# Universal_Receiver.net
KiCad netlist of a schematic drawn in EasyEDA Pro
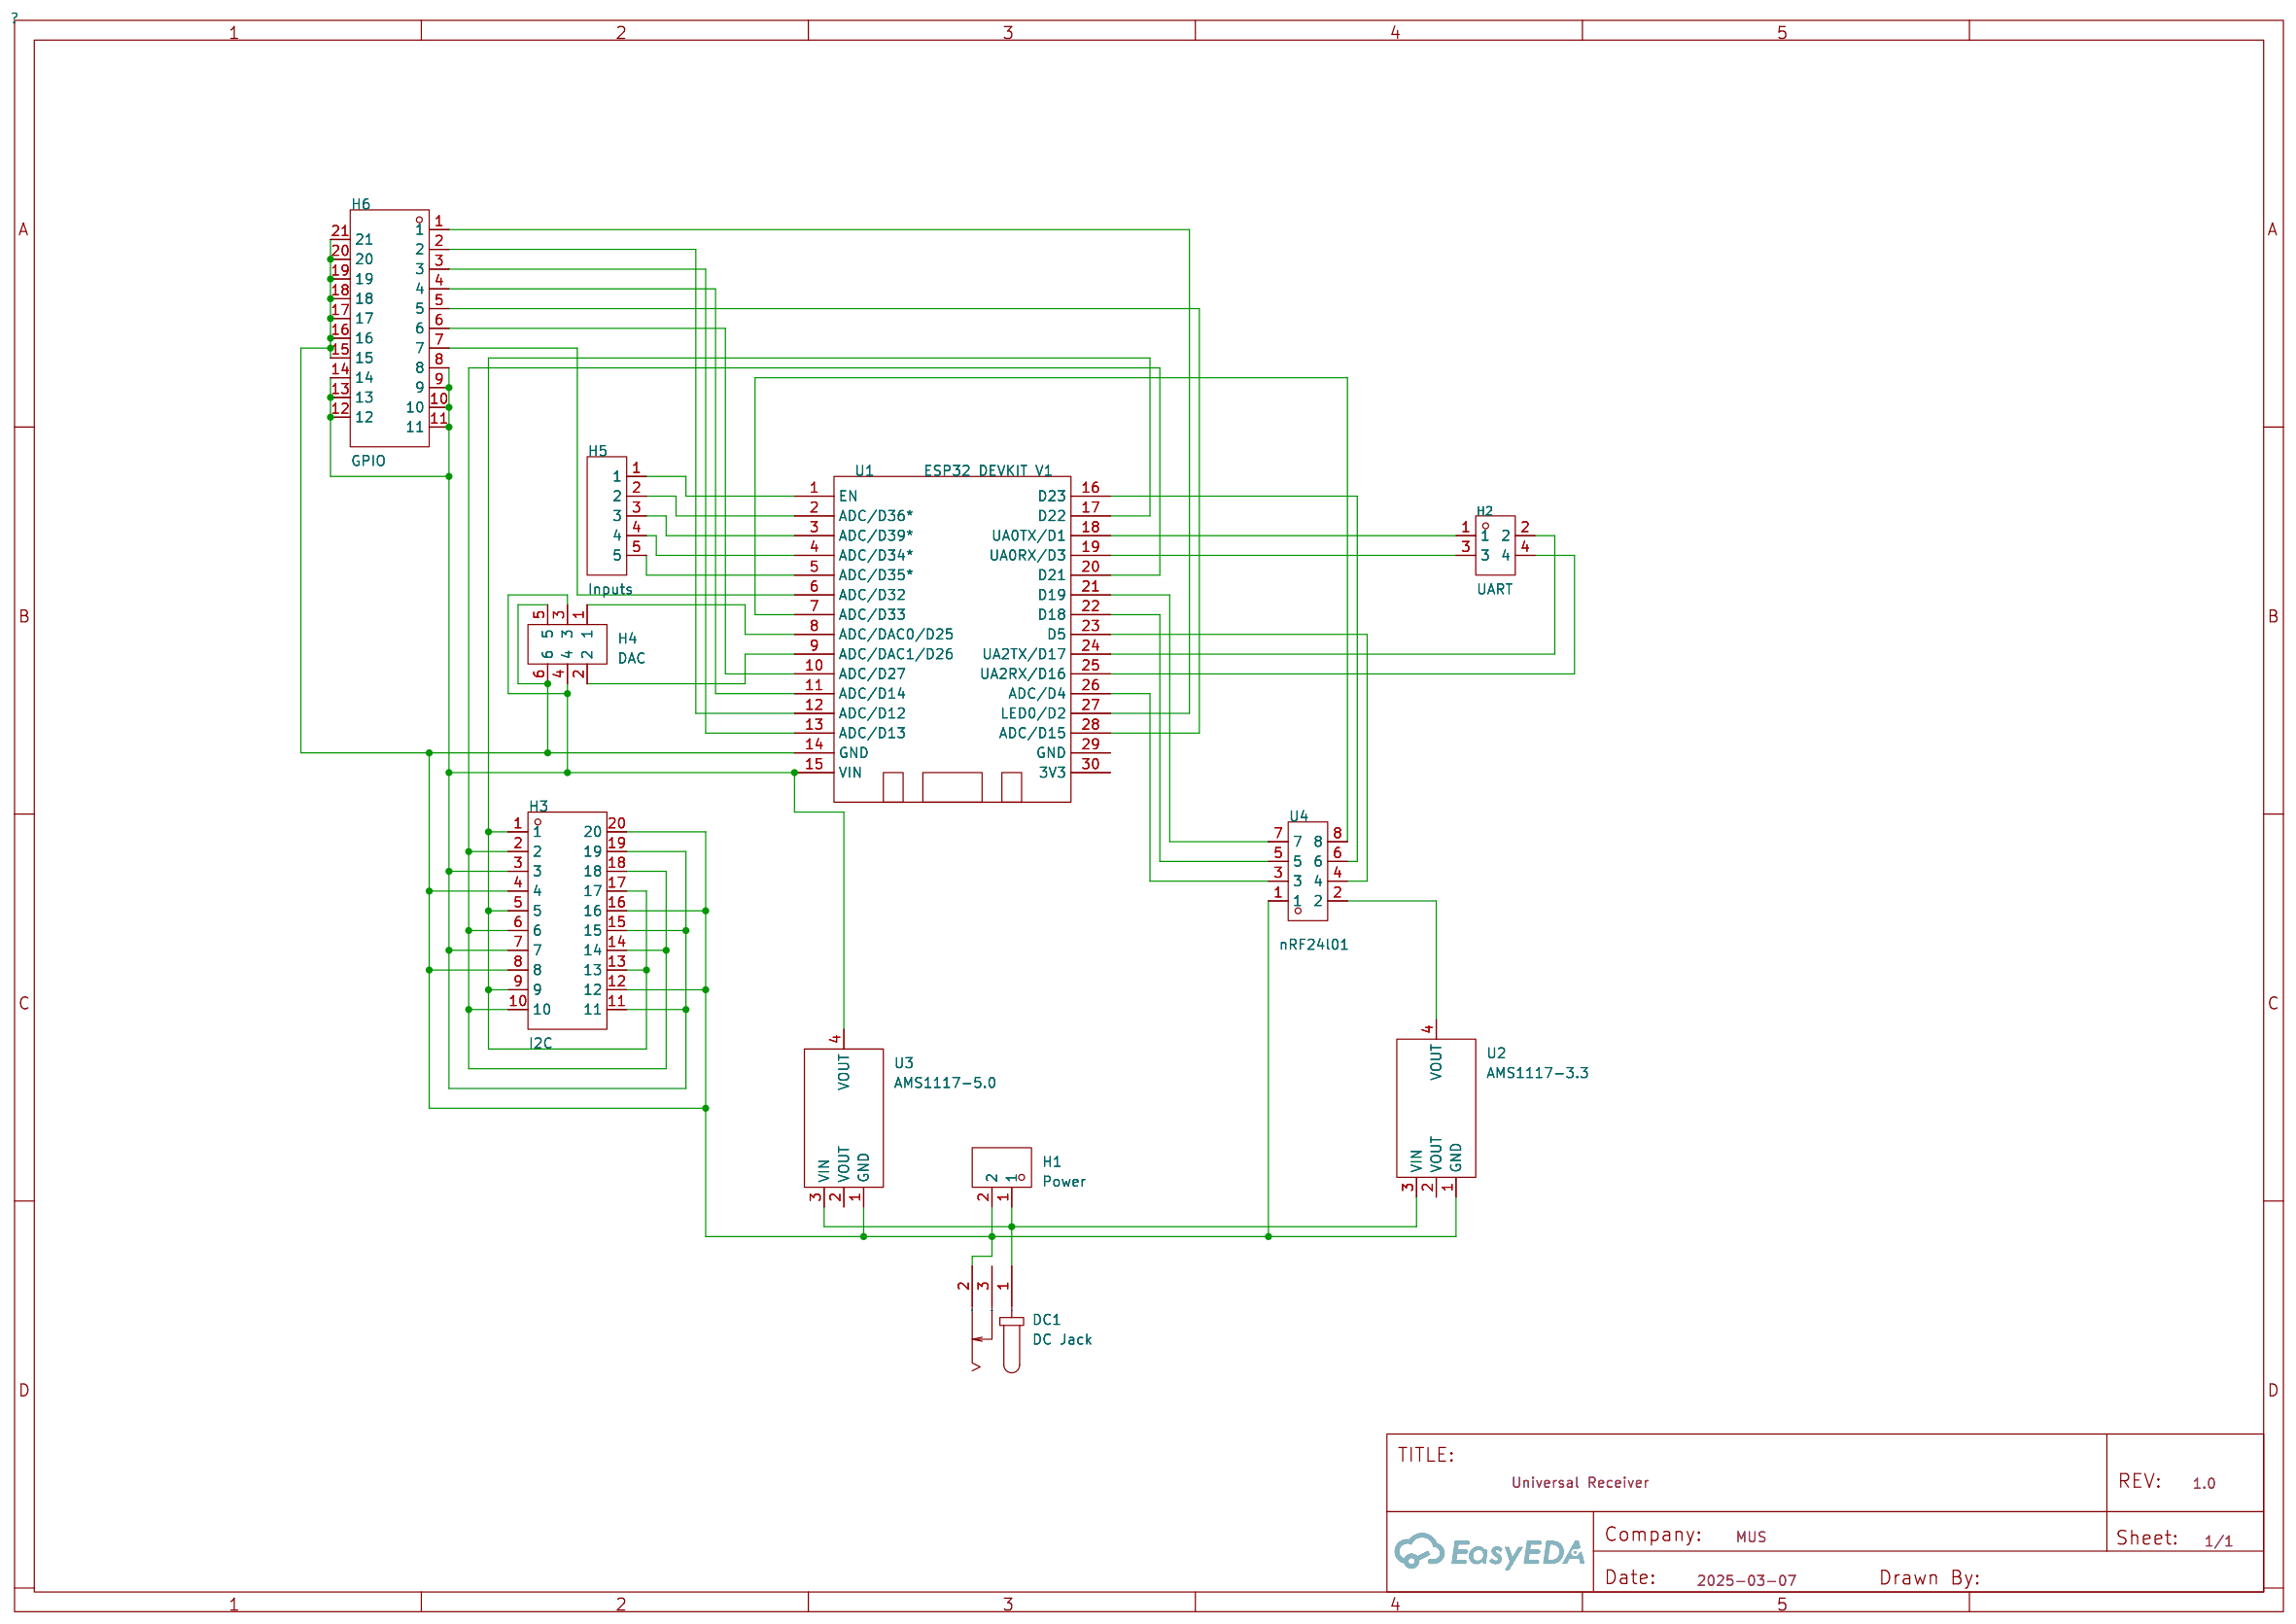
[diagram p0: schematic sheet]

(export (version "E")
  (design (tool "Eeschema 10.0.6"))
  (components
    (comp (ref "DC1")
      (value "DC Jack")
      (footprint "easyedapro:DC-IN-TH_DC-005-5A-2.0")
      (fields (field (name "Manufacturer") "XKB Connection(中国星坤)"))
      (libsource (lib "easyedapro") (part "DC-005-5A-2.0"))
    )
    (comp (ref "H1")
      (value "Power")
      (footprint "easyedapro:HDR-TH_2P-P2.54-V-M_5")
      (fields (field (name "Manufacturer") "HCTL(华灿天禄)"))
      (libsource (lib "easyedapro") (part "PZ254-1-02-Z-C"))
    )
    (comp (ref "H2")
      (value "UART")
      (footprint "easyedapro:HDR-TH_4P-P2.54-V-M-R2-C2-S2.54")
      (fields (field (name "Manufacturer") "HCTL(华灿天禄)"))
      (libsource (lib "easyedapro") (part "PZ254-2-02-Z-2.5-G1"))
    )
    (comp (ref "H3")
      (value "I2C")
      (footprint "easyedapro:HDR-TH_20P-P2.54-V-M-R4-C5-S2.54")
      (fields (field (name "Manufacturer") "hanxia(韩下)"))
      (libsource (lib "easyedapro") (part "HX PZ2.54-4X5P ZZ"))
    )
    (comp (ref "H4")
      (value "DAC")
      (footprint "easyedapro:HDR-TH_6P-P2.54-V-M-R2-C3-S2.54")
      (description "Pin Structure:2x3P Pitch:2.54mm Mounting Type:Straight Number of Rows:Double Row Number of Pins:6P")
      (fields (field (name "Manufacturer") "CONNFLY"))
      (libsource (lib "easyedapro") (part "DS1021-2X3SF11-B"))
    )
    (comp (ref "H5")
      (value "Inputs")
      (footprint "easyedapro:HDR-TH_5P-P2.54-V-M")
      (fields (field (name "Manufacturer") "XFCN(兴飞)"))
      (libsource (lib "easyedapro") (part "PZ254V-11-05P"))
    )
    (comp (ref "H6")
      (value "GPIO")
      (footprint "easyedapro:CONN-TH_HX-PZ2.54-3X7P-ZZ")
      (fields (field (name "Manufacturer") "hanxia(韩下)"))
      (libsource (lib "easyedapro") (part "HX PZ2.54-3X7P ZZ"))
    )
    (comp (ref "U1") (value "ESP32 DEVKIT V1") (libsource (lib "easyedapro") (part "ESP32 DEVKIT V1 DOIT")))
    (comp (ref "U2")
      (value "AMS1117-3.3")
      (footprint "easyedapro:SOT-223-3_L6.5-W3.4-P2.30-LS7.0-BR")
      (fields (field (name "Manufacturer") "AMS"))
      (libsource (lib "easyedapro") (part "AMS1117-3.3"))
    )
    (comp (ref "U3")
      (value "AMS1117-5.0")
      (footprint "easyedapro:SOT-223_L6.5-W3.5-P2.30-LS7.0-BR")
      (fields (field (name "Manufacturer") "AMS"))
      (libsource (lib "easyedapro") (part "AMS1117-5.0"))
    )
    (comp (ref "U4")
      (value "nRF24l01")
      (footprint "easyedapro:HDR-TH_8P-P2.54-V-F-R2-C4-S2.54")
      (fields (field (name "Manufacturer") "ZHOURI(洲日)"))
      (libsource (lib "easyedapro") (part "2.54-2*4"))
    )
  )
  (nets
    (net (code "1") (name "Net-(U1-ADC{slash}D4)") (class "Default")
      (node (ref "U1") (pin "26") (pinfunction "ADC/D4_26") (pintype "bidirectional"))
      (node (ref "U4") (pin "3") (pinfunction "3_3") (pintype "unspecified"))
    )
    (net (code "2") (name "Net-(U1-ADC{slash}D12)") (class "Default")
      (node (ref "H6") (pin "2") (pinfunction "2_2") (pintype "unspecified"))
      (node (ref "U1") (pin "12") (pinfunction "ADC/D12_12") (pintype "bidirectional"))
    )
    (net (code "3") (name "Net-(U1-ADC{slash}D13)") (class "Default")
      (node (ref "H6") (pin "3") (pinfunction "3_3") (pintype "unspecified"))
      (node (ref "U1") (pin "13") (pinfunction "ADC/D13_13") (pintype "bidirectional"))
    )
    (net (code "4") (name "Net-(U1-ADC{slash}D14)") (class "Default")
      (node (ref "H6") (pin "4") (pinfunction "4_4") (pintype "unspecified"))
      (node (ref "U1") (pin "11") (pinfunction "ADC/D14_11") (pintype "bidirectional"))
    )
    (net (code "5") (name "Net-(U1-ADC{slash}D15)") (class "Default")
      (node (ref "H6") (pin "5") (pinfunction "5_5") (pintype "unspecified"))
      (node (ref "U1") (pin "28") (pinfunction "ADC/D15_28") (pintype "bidirectional"))
    )
    (net (code "6") (name "Net-(U1-ADC{slash}D27)") (class "Default")
      (node (ref "H6") (pin "6") (pinfunction "6_6") (pintype "unspecified"))
      (node (ref "U1") (pin "10") (pinfunction "ADC/D27_10") (pintype "bidirectional"))
    )
    (net (code "7") (name "Net-(U1-ADC{slash}D32)") (class "Default")
      (node (ref "H6") (pin "7") (pinfunction "7_7") (pintype "unspecified"))
      (node (ref "U1") (pin "6") (pinfunction "ADC/D32_6") (pintype "bidirectional"))
    )
    (net (code "8") (name "Net-(U1-ADC{slash}D33)") (class "Default")
      (node (ref "U1") (pin "7") (pinfunction "ADC/D33_7") (pintype "bidirectional"))
      (node (ref "U4") (pin "8") (pinfunction "8_8") (pintype "unspecified"))
    )
    (net (code "9") (name "Net-(U1-ADC{slash}D34*)") (class "Default")
      (node (ref "H5") (pin "4") (pinfunction "4_4") (pintype "unspecified"))
      (node (ref "U1") (pin "4") (pinfunction "ADC/D34*_4") (pintype "input"))
    )
    (net (code "10") (name "Net-(U1-ADC{slash}D35*)") (class "Default")
      (node (ref "H5") (pin "5") (pinfunction "5_5") (pintype "unspecified"))
      (node (ref "U1") (pin "5") (pinfunction "ADC/D35*_5") (pintype "input"))
    )
    (net (code "11") (name "Net-(U1-ADC{slash}D36*)") (class "Default")
      (node (ref "H5") (pin "2") (pinfunction "2_2") (pintype "unspecified"))
      (node (ref "U1") (pin "2") (pinfunction "ADC/D36*_2") (pintype "input"))
    )
    (net (code "12") (name "Net-(U1-ADC{slash}D39*)") (class "Default")
      (node (ref "H5") (pin "3") (pinfunction "3_3") (pintype "unspecified"))
      (node (ref "U1") (pin "3") (pinfunction "ADC/D39*_3") (pintype "input"))
    )
    (net (code "13") (name "Net-(U1-ADC{slash}DAC0{slash}D25)") (class "Default")
      (node (ref "H4") (pin "1") (pinfunction "1_1") (pintype "unspecified"))
      (node (ref "U1") (pin "8") (pinfunction "ADC/DAC0/D25_8") (pintype "bidirectional"))
    )
    (net (code "14") (name "Net-(U1-ADC{slash}DAC1{slash}D26)") (class "Default")
      (node (ref "H4") (pin "2") (pinfunction "2_2") (pintype "unspecified"))
      (node (ref "U1") (pin "9") (pinfunction "ADC/DAC1/D26_9") (pintype "bidirectional"))
    )
    (net (code "15") (name "Net-(U1-D5)") (class "Default")
      (node (ref "U1") (pin "23") (pinfunction "D5_23") (pintype "bidirectional"))
      (node (ref "U4") (pin "4") (pinfunction "4_4") (pintype "unspecified"))
    )
    (net (code "16") (name "Net-(U1-D18)") (class "Default")
      (node (ref "U1") (pin "22") (pinfunction "D18_22") (pintype "bidirectional"))
      (node (ref "U4") (pin "5") (pinfunction "5_5") (pintype "unspecified"))
    )
    (net (code "17") (name "Net-(U1-D19)") (class "Default")
      (node (ref "U1") (pin "21") (pinfunction "D19_21") (pintype "bidirectional"))
      (node (ref "U4") (pin "7") (pinfunction "7_7") (pintype "unspecified"))
    )
    (net (code "18") (name "Net-(U1-D21)") (class "Default")
      (node (ref "H3") (pin "10") (pinfunction "10_10") (pintype "unspecified"))
      (node (ref "H3") (pin "14") (pinfunction "14_14") (pintype "unspecified"))
      (node (ref "H3") (pin "18") (pinfunction "18_18") (pintype "unspecified"))
      (node (ref "H3") (pin "2") (pinfunction "2_2") (pintype "unspecified"))
      (node (ref "H3") (pin "6") (pinfunction "6_6") (pintype "unspecified"))
      (node (ref "U1") (pin "20") (pinfunction "D21_20") (pintype "bidirectional"))
    )
    (net (code "19") (name "Net-(U1-D22)") (class "Default")
      (node (ref "H3") (pin "1") (pinfunction "1_1") (pintype "unspecified"))
      (node (ref "H3") (pin "13") (pinfunction "13_13") (pintype "unspecified"))
      (node (ref "H3") (pin "17") (pinfunction "17_17") (pintype "unspecified"))
      (node (ref "H3") (pin "5") (pinfunction "5_5") (pintype "unspecified"))
      (node (ref "H3") (pin "9") (pinfunction "9_9") (pintype "unspecified"))
      (node (ref "U1") (pin "17") (pinfunction "D22_17") (pintype "bidirectional"))
    )
    (net (code "20") (name "Net-(U1-D23)") (class "Default")
      (node (ref "U1") (pin "16") (pinfunction "D23_16") (pintype "bidirectional"))
      (node (ref "U4") (pin "6") (pinfunction "6_6") (pintype "unspecified"))
    )
    (net (code "21") (name "Net-(U1-EN)") (class "Default")
      (node (ref "H5") (pin "1") (pinfunction "1_1") (pintype "unspecified"))
      (node (ref "U1") (pin "1") (pinfunction "EN_1") (pintype "bidirectional"))
    )
    (net (code "22") (name "Net-(U1-LED0{slash}D2)") (class "Default")
      (node (ref "H6") (pin "1") (pinfunction "1_1") (pintype "unspecified"))
      (node (ref "U1") (pin "27") (pinfunction "LED0/D2_27") (pintype "bidirectional"))
    )
    (net (code "23") (name "Net-(U1-UA0RX{slash}D3)") (class "Default")
      (node (ref "H2") (pin "3") (pinfunction "3_3") (pintype "input"))
      (node (ref "U1") (pin "19") (pinfunction "UA0RX/D3_19") (pintype "bidirectional"))
    )
    (net (code "24") (name "Net-(U1-UA0TX{slash}D1)") (class "Default")
      (node (ref "H2") (pin "1") (pinfunction "1_1") (pintype "input"))
      (node (ref "U1") (pin "18") (pinfunction "UA0TX/D1_18") (pintype "bidirectional"))
    )
    (net (code "25") (name "Net-(U1-UA2RX{slash}D16)") (class "Default")
      (node (ref "H2") (pin "4") (pinfunction "4_4") (pintype "input"))
      (node (ref "U1") (pin "25") (pinfunction "UA2RX/D16_25") (pintype "bidirectional"))
    )
    (net (code "26") (name "Net-(U1-UA2TX{slash}D17)") (class "Default")
      (node (ref "H2") (pin "2") (pinfunction "2_2") (pintype "input"))
      (node (ref "U1") (pin "24") (pinfunction "UA2TX/D17_24") (pintype "bidirectional"))
    )
    (net (code "27") (name "Net-(U1-VIN)") (class "Default")
      (node (ref "H3") (pin "11") (pinfunction "11_11") (pintype "unspecified"))
      (node (ref "H3") (pin "15") (pinfunction "15_15") (pintype "unspecified"))
      (node (ref "H3") (pin "19") (pinfunction "19_19") (pintype "unspecified"))
      (node (ref "H3") (pin "3") (pinfunction "3_3") (pintype "unspecified"))
      (node (ref "H3") (pin "7") (pinfunction "7_7") (pintype "unspecified"))
      (node (ref "H4") (pin "3") (pinfunction "3_3") (pintype "unspecified"))
      (node (ref "H4") (pin "4") (pinfunction "4_4") (pintype "unspecified"))
      (node (ref "H6") (pin "10") (pinfunction "10_10") (pintype "unspecified"))
      (node (ref "H6") (pin "11") (pinfunction "11_11") (pintype "unspecified"))
      (node (ref "H6") (pin "12") (pinfunction "12_12") (pintype "unspecified"))
      (node (ref "H6") (pin "13") (pinfunction "13_13") (pintype "unspecified"))
      (node (ref "H6") (pin "14") (pinfunction "14_14") (pintype "unspecified"))
      (node (ref "H6") (pin "8") (pinfunction "8_8") (pintype "unspecified"))
      (node (ref "H6") (pin "9") (pinfunction "9_9") (pintype "unspecified"))
      (node (ref "U1") (pin "15") (pinfunction "VIN_15") (pintype "input"))
      (node (ref "U3") (pin "4") (pinfunction "VOUT_4") (pintype "unspecified"))
    )
    (net (code "28") (name "Net-(U2-GND)") (class "Default")
      (node (ref "DC1") (pin "2") (pinfunction "2_2") (pintype "unspecified"))
      (node (ref "H1") (pin "2") (pinfunction "2_2") (pintype "unspecified"))
      (node (ref "H3") (pin "12") (pinfunction "12_12") (pintype "unspecified"))
      (node (ref "H3") (pin "16") (pinfunction "16_16") (pintype "unspecified"))
      (node (ref "H3") (pin "20") (pinfunction "20_20") (pintype "unspecified"))
      (node (ref "H3") (pin "4") (pinfunction "4_4") (pintype "unspecified"))
      (node (ref "H3") (pin "8") (pinfunction "8_8") (pintype "unspecified"))
      (node (ref "H4") (pin "5") (pinfunction "5_5") (pintype "unspecified"))
      (node (ref "H4") (pin "6") (pinfunction "6_6") (pintype "unspecified"))
      (node (ref "H6") (pin "15") (pinfunction "15_15") (pintype "unspecified"))
      (node (ref "H6") (pin "16") (pinfunction "16_16") (pintype "unspecified"))
      (node (ref "H6") (pin "17") (pinfunction "17_17") (pintype "unspecified"))
      (node (ref "H6") (pin "18") (pinfunction "18_18") (pintype "unspecified"))
      (node (ref "H6") (pin "19") (pinfunction "19_19") (pintype "unspecified"))
      (node (ref "H6") (pin "20") (pinfunction "20_20") (pintype "unspecified"))
      (node (ref "H6") (pin "21") (pinfunction "21_21") (pintype "unspecified"))
      (node (ref "U1") (pin "14") (pinfunction "GND_14") (pintype "bidirectional"))
      (node (ref "U2") (pin "1") (pinfunction "GND_1") (pintype "unspecified"))
      (node (ref "U3") (pin "1") (pinfunction "GND_1") (pintype "unspecified"))
      (node (ref "U4") (pin "1") (pinfunction "1_1") (pintype "unspecified"))
    )
    (net (code "29") (name "Net-(U2-VIN)") (class "Default")
      (node (ref "DC1") (pin "1") (pinfunction "1_1") (pintype "unspecified"))
      (node (ref "H1") (pin "1") (pinfunction "1_1") (pintype "unspecified"))
      (node (ref "U2") (pin "3") (pinfunction "VIN_3") (pintype "unspecified"))
      (node (ref "U3") (pin "3") (pinfunction "VIN_3") (pintype "unspecified"))
    )
    (net (code "30") (name "Net-(U2-VOUT-Pad4)") (class "Default")
      (node (ref "U2") (pin "4") (pinfunction "VOUT_4") (pintype "unspecified"))
      (node (ref "U4") (pin "2") (pinfunction "2_2") (pintype "unspecified"))
    )
    (net (code "31") (name "unconnected-(DC1-Pad3)") (class "Default")
      (node (ref "DC1") (pin "3") (pinfunction "3_3") (pintype "unspecified"))
    )
    (net (code "32") (name "unconnected-(U1-3V3-Pad30)") (class "Default")
      (node (ref "U1") (pin "30") (pinfunction "3V3_30") (pintype "bidirectional"))
    )
    (net (code "33") (name "unconnected-(U1-GND-Pad29)") (class "Default")
      (node (ref "U1") (pin "29") (pinfunction "GND_29") (pintype "bidirectional"))
    )
    (net (code "34") (name "unconnected-(U2-VOUT-Pad2)") (class "Default")
      (node (ref "U2") (pin "2") (pinfunction "VOUT_2") (pintype "unspecified"))
    )
    (net (code "35") (name "unconnected-(U3-VOUT-Pad2)") (class "Default")
      (node (ref "U3") (pin "2") (pinfunction "VOUT_2") (pintype "unspecified"))
    )
  )
)
